# robot.net
KiCad netlist of a schematic drawn in EAGLE
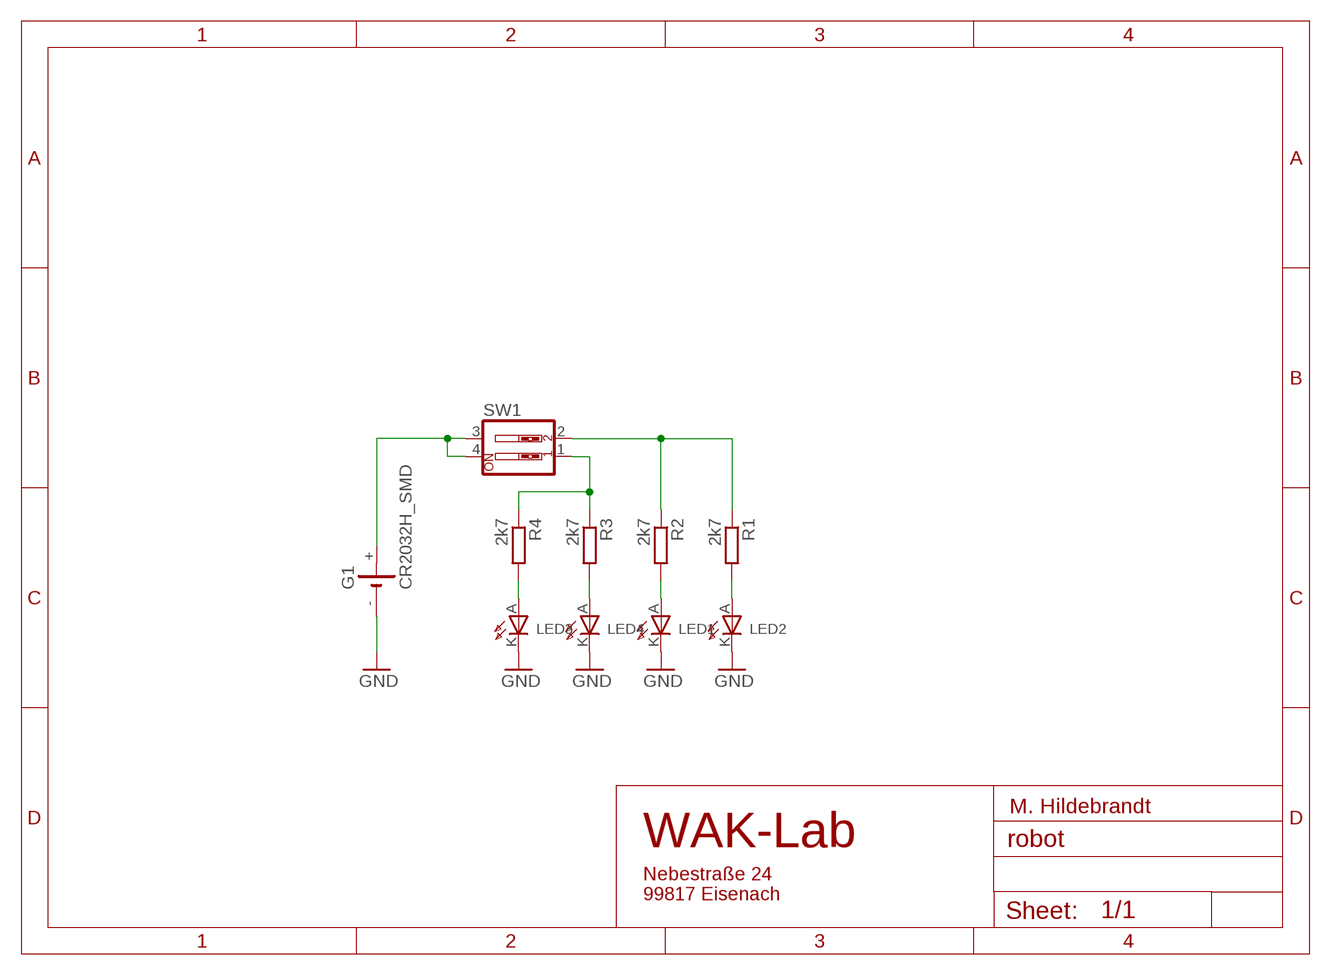
[diagram p0: schematic, sheet 1]

(export (version "E")
  (design (tool "Eeschema 10.0.6"))
  (components
    (comp (ref "G1")
      (value "CR2032H_SMD")
      (footprint "eagle-import:CR2032H_SMD")
      (libsource (lib "eagle-import") (part "CR2032H_SMD"))
    )
    (comp (ref "LED1")
      (value "LEDREAR")
      (footprint "eagle-import:3MM_REAR")
      (libsource (lib "eagle-import") (part "LEDREAR"))
    )
    (comp (ref "LED2")
      (value "LEDREAR")
      (footprint "eagle-import:3MM_REAR")
      (libsource (lib "eagle-import") (part "LEDREAR"))
    )
    (comp (ref "LED3")
      (value "LED3MMH")
      (footprint "eagle-import:3MM_H")
      (libsource (lib "eagle-import") (part "LED3MMH"))
    )
    (comp (ref "LED4")
      (value "LED3MMH")
      (footprint "eagle-import:3MM_H")
      (libsource (lib "eagle-import") (part "LED3MMH"))
    )
    (comp (ref "R1")
      (value "2k7")
      (footprint "eagle-import:0204_7")
      (libsource (lib "eagle-import") (part "R-EU_0204/7"))
    )
    (comp (ref "R2")
      (value "2k7")
      (footprint "eagle-import:0204_7")
      (libsource (lib "eagle-import") (part "R-EU_0204/7"))
    )
    (comp (ref "R3")
      (value "2k7")
      (footprint "eagle-import:0204_7")
      (libsource (lib "eagle-import") (part "R-EU_0204/7"))
    )
    (comp (ref "R4")
      (value "2k7")
      (footprint "eagle-import:0204_7")
      (libsource (lib "eagle-import") (part "R-EU_0204/7"))
    )
    (comp (ref "SW1")
      (value "SW_DIP-2")
      (footprint "eagle-import:EDG-02")
      (libsource (lib "eagle-import") (part "SW_DIP-2"))
    )
  )
  (nets
    (net (code "1") (name "GND") (class "Default")
      (node (ref "G1") (pin "-") (pinfunction "-_-") (pintype "passive"))
      (node (ref "LED1") (pin "K") (pinfunction "K_K") (pintype "passive"))
      (node (ref "LED2") (pin "K") (pinfunction "K_K") (pintype "passive"))
      (node (ref "LED3") (pin "K") (pinfunction "K_K") (pintype "passive"))
      (node (ref "LED4") (pin "K") (pinfunction "K_K") (pintype "passive"))
    )
    (net (code "2") (name "Net-(G1-Pad+)") (class "Default")
      (node (ref "G1") (pin "+") (pinfunction "+_+") (pintype "passive"))
      (node (ref "SW1") (pin "3") (pinfunction "3_3") (pintype "passive"))
      (node (ref "SW1") (pin "4") (pinfunction "4_4") (pintype "passive"))
    )
    (net (code "3") (name "Net-(LED1-PadA)") (class "Default")
      (node (ref "LED1") (pin "A") (pinfunction "A_A") (pintype "passive"))
      (node (ref "R2") (pin "2") (pinfunction "2_2") (pintype "passive"))
    )
    (net (code "4") (name "Net-(LED2-PadA)") (class "Default")
      (node (ref "LED2") (pin "A") (pinfunction "A_A") (pintype "passive"))
      (node (ref "R1") (pin "2") (pinfunction "2_2") (pintype "passive"))
    )
    (net (code "5") (name "Net-(LED3-PadA)") (class "Default")
      (node (ref "LED3") (pin "A") (pinfunction "A_A") (pintype "passive"))
      (node (ref "R4") (pin "2") (pinfunction "2_2") (pintype "passive"))
    )
    (net (code "6") (name "Net-(LED4-PadA)") (class "Default")
      (node (ref "LED4") (pin "A") (pinfunction "A_A") (pintype "passive"))
      (node (ref "R3") (pin "2") (pinfunction "2_2") (pintype "passive"))
    )
    (net (code "7") (name "Net-(R1-Pad1)") (class "Default")
      (node (ref "R1") (pin "1") (pinfunction "1_1") (pintype "passive"))
      (node (ref "R2") (pin "1") (pinfunction "1_1") (pintype "passive"))
      (node (ref "SW1") (pin "2") (pinfunction "2_2") (pintype "passive"))
    )
    (net (code "8") (name "Net-(R3-Pad1)") (class "Default")
      (node (ref "R3") (pin "1") (pinfunction "1_1") (pintype "passive"))
      (node (ref "R4") (pin "1") (pinfunction "1_1") (pintype "passive"))
      (node (ref "SW1") (pin "1") (pinfunction "1_1") (pintype "passive"))
    )
  )
)
